# electrode_tester.net
KiCad netlist of a schematic drawn in EAGLE
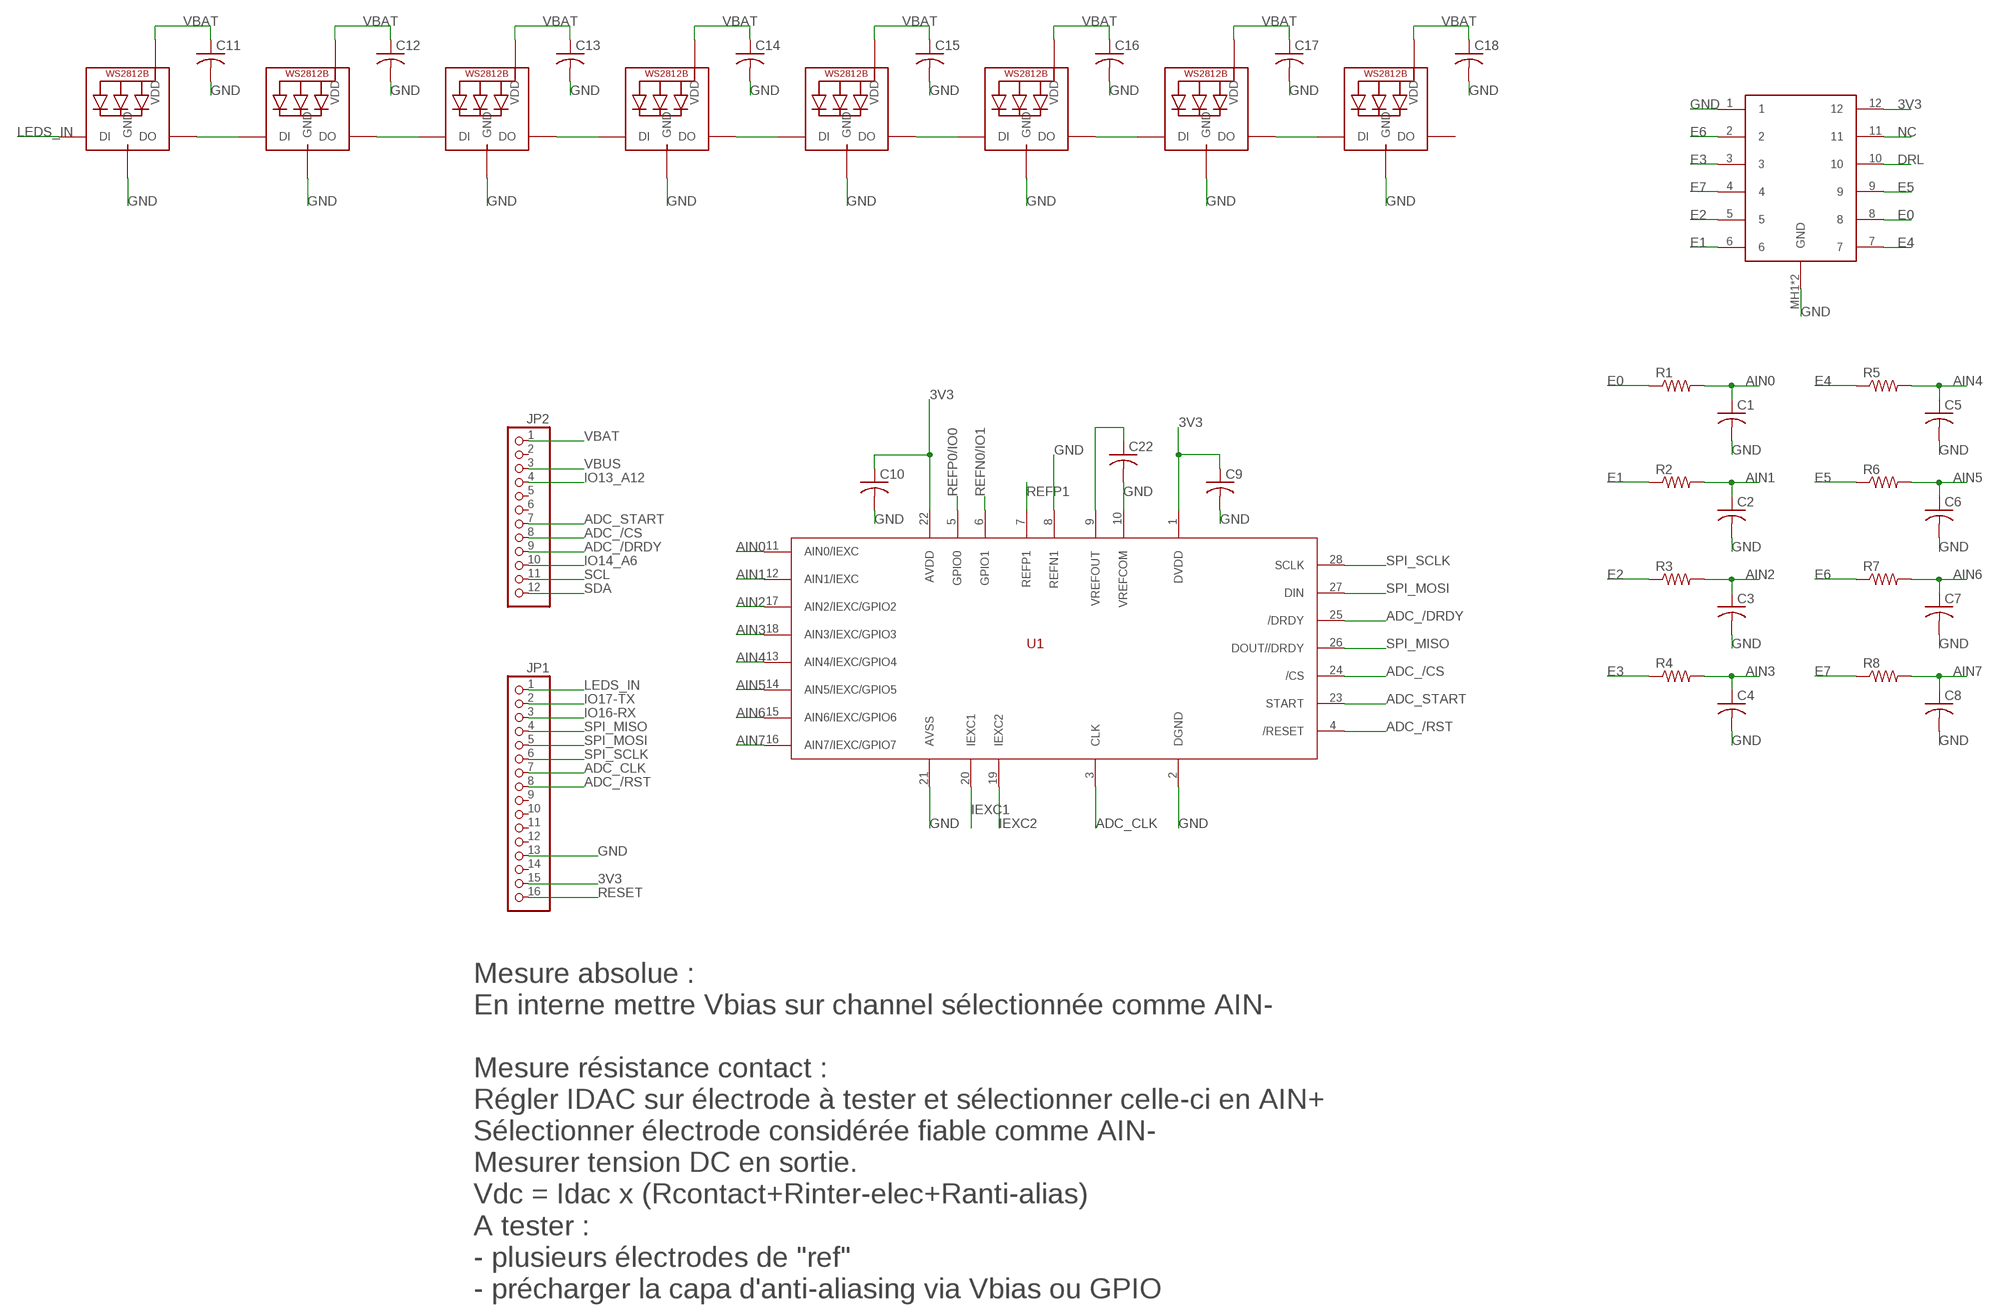
[diagram p0: schematic, sheet 1, part 1 of 2]
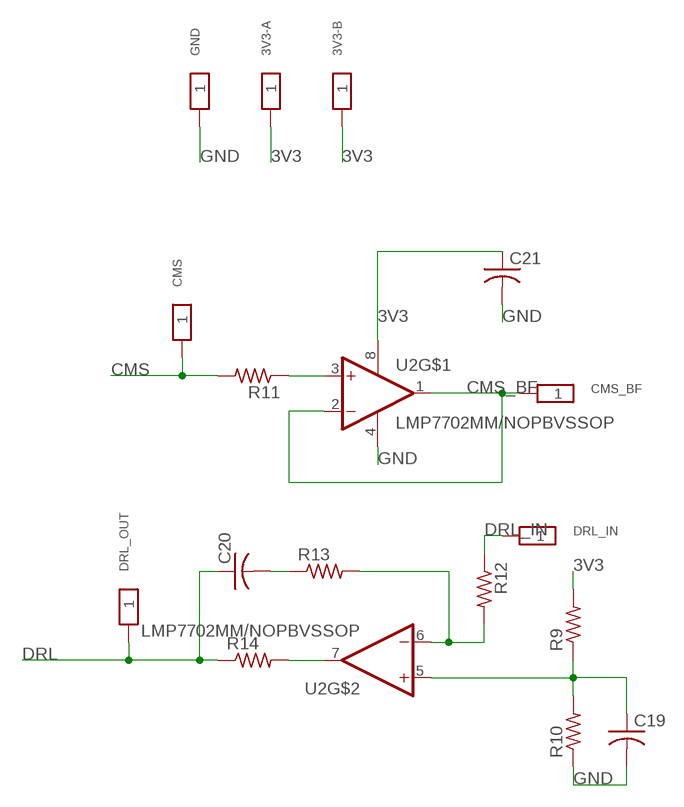
[diagram p1: schematic, sheet 1, part 2 of 2]

(export (version "E")
  (design (tool "Eeschema 10.0.6"))
  (components
    (comp (ref "3V3-A")
      (value "TESTPAD_PROG")
      (footprint "eagle-import:TP1.5MM")
      (libsource (lib "eagle-import") (part "TESTPAD_PROG"))
    )
    (comp (ref "3V3-B")
      (value "TESTPAD_PROG")
      (footprint "eagle-import:TP1.5MM")
      (libsource (lib "eagle-import") (part "TESTPAD_PROG"))
    )
    (comp (ref "C1")
      (value "C-USC0603")
      (footprint "eagle-import:C0603")
      (libsource (lib "eagle-import") (part "C-USC0603"))
    )
    (comp (ref "C2")
      (value "C-USC0603")
      (footprint "eagle-import:C0603")
      (libsource (lib "eagle-import") (part "C-USC0603"))
    )
    (comp (ref "C3")
      (value "C-USC0603")
      (footprint "eagle-import:C0603")
      (libsource (lib "eagle-import") (part "C-USC0603"))
    )
    (comp (ref "C4")
      (value "C-USC0603")
      (footprint "eagle-import:C0603")
      (libsource (lib "eagle-import") (part "C-USC0603"))
    )
    (comp (ref "C5")
      (value "C-USC0603")
      (footprint "eagle-import:C0603")
      (libsource (lib "eagle-import") (part "C-USC0603"))
    )
    (comp (ref "C6")
      (value "C-USC0603")
      (footprint "eagle-import:C0603")
      (libsource (lib "eagle-import") (part "C-USC0603"))
    )
    (comp (ref "C7")
      (value "C-USC0603")
      (footprint "eagle-import:C0603")
      (libsource (lib "eagle-import") (part "C-USC0603"))
    )
    (comp (ref "C8")
      (value "C-USC0603")
      (footprint "eagle-import:C0603")
      (libsource (lib "eagle-import") (part "C-USC0603"))
    )
    (comp (ref "C9")
      (value "C-USC0603")
      (footprint "eagle-import:C0603")
      (libsource (lib "eagle-import") (part "C-USC0603"))
    )
    (comp (ref "C10")
      (value "C-USC0603")
      (footprint "eagle-import:C0603")
      (libsource (lib "eagle-import") (part "C-USC0603"))
    )
    (comp (ref "C11")
      (value "C-USC0603")
      (footprint "eagle-import:C0603")
      (libsource (lib "eagle-import") (part "C-USC0603"))
    )
    (comp (ref "C12")
      (value "C-USC0603")
      (footprint "eagle-import:C0603")
      (libsource (lib "eagle-import") (part "C-USC0603"))
    )
    (comp (ref "C13")
      (value "C-USC0603")
      (footprint "eagle-import:C0603")
      (libsource (lib "eagle-import") (part "C-USC0603"))
    )
    (comp (ref "C14")
      (value "C-USC0603")
      (footprint "eagle-import:C0603")
      (libsource (lib "eagle-import") (part "C-USC0603"))
    )
    (comp (ref "C15")
      (value "C-USC0603")
      (footprint "eagle-import:C0603")
      (libsource (lib "eagle-import") (part "C-USC0603"))
    )
    (comp (ref "C16")
      (value "C-USC0603")
      (footprint "eagle-import:C0603")
      (libsource (lib "eagle-import") (part "C-USC0603"))
    )
    (comp (ref "C17")
      (value "C-USC0603")
      (footprint "eagle-import:C0603")
      (libsource (lib "eagle-import") (part "C-USC0603"))
    )
    (comp (ref "C18")
      (value "C-USC0603")
      (footprint "eagle-import:C0603")
      (libsource (lib "eagle-import") (part "C-USC0603"))
    )
    (comp (ref "C19")
      (value "C-USC0603")
      (footprint "eagle-import:C0603")
      (libsource (lib "eagle-import") (part "C-USC0603"))
    )
    (comp (ref "C20")
      (value "C-USC0603")
      (footprint "eagle-import:C0603")
      (libsource (lib "eagle-import") (part "C-USC0603"))
    )
    (comp (ref "C21")
      (value "C-USC0603")
      (footprint "eagle-import:C0603")
      (libsource (lib "eagle-import") (part "C-USC0603"))
    )
    (comp (ref "C22")
      (value "C-USC0603")
      (footprint "eagle-import:C0603")
      (libsource (lib "eagle-import") (part "C-USC0603"))
    )
    (comp (ref "CMS")
      (value "TESTPAD_PROG")
      (footprint "eagle-import:TP1.5MM")
      (libsource (lib "eagle-import") (part "TESTPAD_PROG"))
    )
    (comp (ref "CMS_BF")
      (value "TESTPAD_PROG")
      (footprint "eagle-import:TP1.5MM")
      (libsource (lib "eagle-import") (part "TESTPAD_PROG"))
    )
    (comp (ref "CONN1")
      (value "505110-1292")
      (footprint "eagle-import:505110-1292")
      (libsource (lib "eagle-import") (part "505110-1292"))
    )
    (comp (ref "DRL_IN")
      (value "TESTPAD_PROG")
      (footprint "eagle-import:TP1.5MM")
      (libsource (lib "eagle-import") (part "TESTPAD_PROG"))
    )
    (comp (ref "DRL_OUT")
      (value "TESTPAD_PROG")
      (footprint "eagle-import:TP1.5MM")
      (libsource (lib "eagle-import") (part "TESTPAD_PROG"))
    )
    (comp (ref "GND")
      (value "TESTPAD_PROG")
      (footprint "eagle-import:TP1.5MM")
      (libsource (lib "eagle-import") (part "TESTPAD_PROG"))
    )
    (comp (ref "JP1")
      (value "HEADER-1X16ROUND")
      (footprint "eagle-import:1X16_ROUND")
      (libsource (lib "eagle-import") (part "HEADER-1X16ROUND"))
    )
    (comp (ref "JP2")
      (value "HEADER-1X12")
      (footprint "eagle-import:1X12_ROUND")
      (libsource (lib "eagle-import") (part "HEADER-1X12"))
    )
    (comp (ref "LED1")
      (value "WS2812B5050")
      (footprint "eagle-import:WS2812B")
      (libsource (lib "eagle-import") (part "WS2812B5050"))
    )
    (comp (ref "LED2")
      (value "WS2812B5050")
      (footprint "eagle-import:WS2812B")
      (libsource (lib "eagle-import") (part "WS2812B5050"))
    )
    (comp (ref "LED3")
      (value "WS2812B5050")
      (footprint "eagle-import:WS2812B")
      (libsource (lib "eagle-import") (part "WS2812B5050"))
    )
    (comp (ref "LED4")
      (value "WS2812B5050")
      (footprint "eagle-import:WS2812B")
      (libsource (lib "eagle-import") (part "WS2812B5050"))
    )
    (comp (ref "LED5")
      (value "WS2812B5050")
      (footprint "eagle-import:WS2812B")
      (libsource (lib "eagle-import") (part "WS2812B5050"))
    )
    (comp (ref "LED6")
      (value "WS2812B5050")
      (footprint "eagle-import:WS2812B")
      (libsource (lib "eagle-import") (part "WS2812B5050"))
    )
    (comp (ref "LED7")
      (value "WS2812B5050")
      (footprint "eagle-import:WS2812B")
      (libsource (lib "eagle-import") (part "WS2812B5050"))
    )
    (comp (ref "LED8")
      (value "WS2812B5050")
      (footprint "eagle-import:WS2812B")
      (libsource (lib "eagle-import") (part "WS2812B5050"))
    )
    (comp (ref "R1")
      (value "R-US_R0603")
      (footprint "eagle-import:R0603")
      (libsource (lib "eagle-import") (part "R-US_R0603"))
    )
    (comp (ref "R2")
      (value "R-US_R0603")
      (footprint "eagle-import:R0603")
      (libsource (lib "eagle-import") (part "R-US_R0603"))
    )
    (comp (ref "R3")
      (value "R-US_R0603")
      (footprint "eagle-import:R0603")
      (libsource (lib "eagle-import") (part "R-US_R0603"))
    )
    (comp (ref "R4")
      (value "R-US_R0603")
      (footprint "eagle-import:R0603")
      (libsource (lib "eagle-import") (part "R-US_R0603"))
    )
    (comp (ref "R5")
      (value "R-US_R0603")
      (footprint "eagle-import:R0603")
      (libsource (lib "eagle-import") (part "R-US_R0603"))
    )
    (comp (ref "R6")
      (value "R-US_R0603")
      (footprint "eagle-import:R0603")
      (libsource (lib "eagle-import") (part "R-US_R0603"))
    )
    (comp (ref "R7")
      (value "R-US_R0603")
      (footprint "eagle-import:R0603")
      (libsource (lib "eagle-import") (part "R-US_R0603"))
    )
    (comp (ref "R8")
      (value "R-US_R0603")
      (footprint "eagle-import:R0603")
      (libsource (lib "eagle-import") (part "R-US_R0603"))
    )
    (comp (ref "R9")
      (value "R-US_R0603")
      (footprint "eagle-import:R0603")
      (libsource (lib "eagle-import") (part "R-US_R0603"))
    )
    (comp (ref "R10")
      (value "R-US_R0603")
      (footprint "eagle-import:R0603")
      (libsource (lib "eagle-import") (part "R-US_R0603"))
    )
    (comp (ref "R11")
      (value "R-US_R0603")
      (footprint "eagle-import:R0603")
      (libsource (lib "eagle-import") (part "R-US_R0603"))
    )
    (comp (ref "R12")
      (value "R-US_R0603")
      (footprint "eagle-import:R0603")
      (libsource (lib "eagle-import") (part "R-US_R0603"))
    )
    (comp (ref "R13")
      (value "R-US_R0603")
      (footprint "eagle-import:R0603")
      (libsource (lib "eagle-import") (part "R-US_R0603"))
    )
    (comp (ref "R14")
      (value "R-US_R0603")
      (footprint "eagle-import:R0603")
      (libsource (lib "eagle-import") (part "R-US_R0603"))
    )
    (comp (ref "U1")
      (value "ADS1248")
      (footprint "eagle-import:TSSOP28")
      (libsource (lib "eagle-import") (part "ADS1248"))
    )
    (comp (ref "U2")
      (value "LMP7702MM/NOPBVSSOP")
      (footprint "eagle-import:VSSOP8")
      (fields (field (name "MF") "Texas Instruments") (field (name "MP") "LMP7702MM/NOPB"))
      (libsource (lib "eagle-import") (part "LMP7702MM/NOPBVSSOP"))
    )
  )
  (nets
    (net (code "1") (name "/3V3") (class "Default")
      (node (ref "3V3-A") (pin "1") (pinfunction "1_1") (pintype "bidirectional"))
      (node (ref "3V3-B") (pin "1") (pinfunction "1_1") (pintype "bidirectional"))
      (node (ref "C10") (pin "1") (pinfunction "1_1") (pintype "passive"))
      (node (ref "C21") (pin "1") (pinfunction "1_1") (pintype "passive"))
      (node (ref "C9") (pin "1") (pinfunction "1_1") (pintype "passive"))
      (node (ref "CONN1") (pin "12") (pinfunction "12_12") (pintype "bidirectional"))
      (node (ref "JP1") (pin "15") (pinfunction "15_15") (pintype "passive"))
      (node (ref "R9") (pin "2") (pinfunction "2_2") (pintype "passive"))
      (node (ref "U1") (pin "1") (pinfunction "DVDD_1") (pintype "bidirectional"))
      (node (ref "U1") (pin "22") (pinfunction "AVDD_22") (pintype "bidirectional"))
      (node (ref "U2") (pin "8") (pinfunction "V+_8") (pintype "power_in"))
    )
    (net (code "2") (name "/ADC_CLK") (class "Default")
      (node (ref "JP1") (pin "7") (pinfunction "7_7") (pintype "passive"))
      (node (ref "U1") (pin "3") (pinfunction "CLK_3") (pintype "bidirectional"))
    )
    (net (code "3") (name "/ADC_START") (class "Default")
      (node (ref "JP2") (pin "7") (pinfunction "7_7") (pintype "passive"))
      (node (ref "U1") (pin "23") (pinfunction "START_23") (pintype "bidirectional"))
    )
    (net (code "4") (name "/ADC_{slash}CS") (class "Default")
      (node (ref "JP2") (pin "8") (pinfunction "8_8") (pintype "passive"))
      (node (ref "U1") (pin "24") (pinfunction "/CS_24") (pintype "bidirectional"))
    )
    (net (code "5") (name "/ADC_{slash}DRDY") (class "Default")
      (node (ref "JP2") (pin "9") (pinfunction "9_9") (pintype "passive"))
      (node (ref "U1") (pin "25") (pinfunction "/DRDY_25") (pintype "bidirectional"))
    )
    (net (code "6") (name "/ADC_{slash}RST") (class "Default")
      (node (ref "JP1") (pin "8") (pinfunction "8_8") (pintype "passive"))
      (node (ref "U1") (pin "4") (pinfunction "/RESET_4") (pintype "bidirectional"))
    )
    (net (code "7") (name "/AIN0") (class "Default")
      (node (ref "C1") (pin "1") (pinfunction "1_1") (pintype "passive"))
      (node (ref "R1") (pin "2") (pinfunction "2_2") (pintype "passive"))
      (node (ref "U1") (pin "11") (pinfunction "AIN0/IEXC_11") (pintype "bidirectional"))
    )
    (net (code "8") (name "/AIN1") (class "Default")
      (node (ref "C2") (pin "1") (pinfunction "1_1") (pintype "passive"))
      (node (ref "R2") (pin "2") (pinfunction "2_2") (pintype "passive"))
      (node (ref "U1") (pin "12") (pinfunction "AIN1/IEXC_12") (pintype "bidirectional"))
    )
    (net (code "9") (name "/AIN2") (class "Default")
      (node (ref "C3") (pin "1") (pinfunction "1_1") (pintype "passive"))
      (node (ref "R3") (pin "2") (pinfunction "2_2") (pintype "passive"))
      (node (ref "U1") (pin "17") (pinfunction "AIN2/IEXC/GPIO2_17") (pintype "bidirectional"))
    )
    (net (code "10") (name "/AIN3") (class "Default")
      (node (ref "C4") (pin "1") (pinfunction "1_1") (pintype "passive"))
      (node (ref "R4") (pin "2") (pinfunction "2_2") (pintype "passive"))
      (node (ref "U1") (pin "18") (pinfunction "AIN3/IEXC/GPIO3_18") (pintype "bidirectional"))
    )
    (net (code "11") (name "/AIN4") (class "Default")
      (node (ref "C5") (pin "1") (pinfunction "1_1") (pintype "passive"))
      (node (ref "R5") (pin "2") (pinfunction "2_2") (pintype "passive"))
      (node (ref "U1") (pin "13") (pinfunction "AIN4/IEXC/GPIO4_13") (pintype "bidirectional"))
    )
    (net (code "12") (name "/AIN5") (class "Default")
      (node (ref "C6") (pin "1") (pinfunction "1_1") (pintype "passive"))
      (node (ref "R6") (pin "2") (pinfunction "2_2") (pintype "passive"))
      (node (ref "U1") (pin "14") (pinfunction "AIN5/IEXC/GPIO5_14") (pintype "bidirectional"))
    )
    (net (code "13") (name "/AIN6") (class "Default")
      (node (ref "C7") (pin "1") (pinfunction "1_1") (pintype "passive"))
      (node (ref "R7") (pin "2") (pinfunction "2_2") (pintype "passive"))
      (node (ref "U1") (pin "15") (pinfunction "AIN6/IEXC/GPIO6_15") (pintype "bidirectional"))
    )
    (net (code "14") (name "/AIN7") (class "Default")
      (node (ref "C8") (pin "1") (pinfunction "1_1") (pintype "passive"))
      (node (ref "R8") (pin "2") (pinfunction "2_2") (pintype "passive"))
      (node (ref "U1") (pin "16") (pinfunction "AIN7/IEXC/GPIO7_16") (pintype "bidirectional"))
    )
    (net (code "15") (name "/CMS") (class "Default")
      (node (ref "CMS") (pin "1") (pinfunction "1_1") (pintype "bidirectional"))
      (node (ref "R11") (pin "2") (pinfunction "2_2") (pintype "passive"))
    )
    (net (code "16") (name "/CMS_BF") (class "Default")
      (node (ref "CMS_BF") (pin "1") (pinfunction "1_1") (pintype "bidirectional"))
      (node (ref "U2") (pin "1") (pinfunction "OUT_1") (pintype "output"))
      (node (ref "U2") (pin "2") (pinfunction "-IN_2") (pintype "input"))
    )
    (net (code "17") (name "/DRL") (class "Default")
      (node (ref "C20") (pin "1") (pinfunction "1_1") (pintype "passive"))
      (node (ref "CONN1") (pin "10") (pinfunction "10_10") (pintype "bidirectional"))
      (node (ref "DRL_OUT") (pin "1") (pinfunction "1_1") (pintype "bidirectional"))
      (node (ref "R14") (pin "1") (pinfunction "1_1") (pintype "passive"))
    )
    (net (code "18") (name "/DRL_IN") (class "Default")
      (node (ref "DRL_IN") (pin "1") (pinfunction "1_1") (pintype "bidirectional"))
      (node (ref "R12") (pin "1") (pinfunction "1_1") (pintype "passive"))
    )
    (net (code "19") (name "/E0") (class "Default")
      (node (ref "CONN1") (pin "8") (pinfunction "8_8") (pintype "bidirectional"))
      (node (ref "R1") (pin "1") (pinfunction "1_1") (pintype "passive"))
    )
    (net (code "20") (name "/E1") (class "Default")
      (node (ref "CONN1") (pin "6") (pinfunction "6_6") (pintype "bidirectional"))
      (node (ref "R2") (pin "1") (pinfunction "1_1") (pintype "passive"))
    )
    (net (code "21") (name "/E2") (class "Default")
      (node (ref "CONN1") (pin "5") (pinfunction "5_5") (pintype "bidirectional"))
      (node (ref "R3") (pin "1") (pinfunction "1_1") (pintype "passive"))
    )
    (net (code "22") (name "/E3") (class "Default")
      (node (ref "CONN1") (pin "3") (pinfunction "3_3") (pintype "bidirectional"))
      (node (ref "R4") (pin "1") (pinfunction "1_1") (pintype "passive"))
    )
    (net (code "23") (name "/E4") (class "Default")
      (node (ref "CONN1") (pin "7") (pinfunction "7_7") (pintype "bidirectional"))
      (node (ref "R5") (pin "1") (pinfunction "1_1") (pintype "passive"))
    )
    (net (code "24") (name "/E5") (class "Default")
      (node (ref "CONN1") (pin "9") (pinfunction "9_9") (pintype "bidirectional"))
      (node (ref "R6") (pin "1") (pinfunction "1_1") (pintype "passive"))
    )
    (net (code "25") (name "/E6") (class "Default")
      (node (ref "CONN1") (pin "2") (pinfunction "2_2") (pintype "bidirectional"))
      (node (ref "R7") (pin "1") (pinfunction "1_1") (pintype "passive"))
    )
    (net (code "26") (name "/E7") (class "Default")
      (node (ref "CONN1") (pin "4") (pinfunction "4_4") (pintype "bidirectional"))
      (node (ref "R8") (pin "1") (pinfunction "1_1") (pintype "passive"))
    )
    (net (code "27") (name "/GND") (class "Default")
      (node (ref "C1") (pin "2") (pinfunction "2_2") (pintype "passive"))
      (node (ref "C10") (pin "2") (pinfunction "2_2") (pintype "passive"))
      (node (ref "C11") (pin "2") (pinfunction "2_2") (pintype "passive"))
      (node (ref "C12") (pin "2") (pinfunction "2_2") (pintype "passive"))
      (node (ref "C13") (pin "2") (pinfunction "2_2") (pintype "passive"))
      (node (ref "C14") (pin "2") (pinfunction "2_2") (pintype "passive"))
      (node (ref "C15") (pin "2") (pinfunction "2_2") (pintype "passive"))
      (node (ref "C16") (pin "2") (pinfunction "2_2") (pintype "passive"))
      (node (ref "C17") (pin "2") (pinfunction "2_2") (pintype "passive"))
      (node (ref "C18") (pin "2") (pinfunction "2_2") (pintype "passive"))
      (node (ref "C19") (pin "2") (pinfunction "2_2") (pintype "passive"))
      (node (ref "C2") (pin "2") (pinfunction "2_2") (pintype "passive"))
      (node (ref "C21") (pin "2") (pinfunction "2_2") (pintype "passive"))
      (node (ref "C22") (pin "2") (pinfunction "2_2") (pintype "passive"))
      (node (ref "C3") (pin "2") (pinfunction "2_2") (pintype "passive"))
      (node (ref "C4") (pin "2") (pinfunction "2_2") (pintype "passive"))
      (node (ref "C5") (pin "2") (pinfunction "2_2") (pintype "passive"))
      (node (ref "C6") (pin "2") (pinfunction "2_2") (pintype "passive"))
      (node (ref "C7") (pin "2") (pinfunction "2_2") (pintype "passive"))
      (node (ref "C8") (pin "2") (pinfunction "2_2") (pintype "passive"))
      (node (ref "C9") (pin "2") (pinfunction "2_2") (pintype "passive"))
      (node (ref "CONN1") (pin "1") (pinfunction "1_1") (pintype "bidirectional"))
      (node (ref "CONN1") (pin "MH1") (pinfunction "GND_MH1") (pintype "bidirectional"))
      (node (ref "CONN1") (pin "MH2") (pinfunction "GND_MH2") (pintype "bidirectional"))
      (node (ref "GND") (pin "1") (pinfunction "1_1") (pintype "bidirectional"))
      (node (ref "JP1") (pin "13") (pinfunction "13_13") (pintype "passive"))
      (node (ref "LED1") (pin "3-GND") (pinfunction "GND_3-GND") (pintype "power_in"))
      (node (ref "LED2") (pin "3-GND") (pinfunction "GND_3-GND") (pintype "power_in"))
      (node (ref "LED3") (pin "3-GND") (pinfunction "GND_3-GND") (pintype "power_in"))
      (node (ref "LED4") (pin "3-GND") (pinfunction "GND_3-GND") (pintype "power_in"))
      (node (ref "LED5") (pin "3-GND") (pinfunction "GND_3-GND") (pintype "power_in"))
      (node (ref "LED6") (pin "3-GND") (pinfunction "GND_3-GND") (pintype "power_in"))
      (node (ref "LED7") (pin "3-GND") (pinfunction "GND_3-GND") (pintype "power_in"))
      (node (ref "LED8") (pin "3-GND") (pinfunction "GND_3-GND") (pintype "power_in"))
      (node (ref "R10") (pin "1") (pinfunction "1_1") (pintype "passive"))
      (node (ref "U1") (pin "10") (pinfunction "VREFCOM_10") (pintype "bidirectional"))
      (node (ref "U1") (pin "2") (pinfunction "DGND_2") (pintype "bidirectional"))
      (node (ref "U1") (pin "21") (pinfunction "AVSS_21") (pintype "bidirectional"))
      (node (ref "U1") (pin "8") (pinfunction "REFN1_8") (pintype "bidirectional"))
      (node (ref "U2") (pin "4") (pinfunction "V-_4") (pintype "power_in"))
    )
    (net (code "28") (name "/IEXC1") (class "Default")
      (node (ref "U1") (pin "20") (pinfunction "IEXC1_20") (pintype "bidirectional"))
    )
    (net (code "29") (name "/IEXC2") (class "Default")
      (node (ref "U1") (pin "19") (pinfunction "IEXC2_19") (pintype "bidirectional"))
    )
    (net (code "30") (name "/IO13_A12") (class "Default")
      (node (ref "JP2") (pin "4") (pinfunction "4_4") (pintype "passive"))
    )
    (net (code "31") (name "/IO14_A6") (class "Default")
      (node (ref "JP2") (pin "10") (pinfunction "10_10") (pintype "passive"))
    )
    (net (code "32") (name "/IO16-RX") (class "Default")
      (node (ref "JP1") (pin "3") (pinfunction "3_3") (pintype "passive"))
    )
    (net (code "33") (name "/IO17-TX") (class "Default")
      (node (ref "JP1") (pin "2") (pinfunction "2_2") (pintype "passive"))
    )
    (net (code "34") (name "/LEDS_IN") (class "Default")
      (node (ref "JP1") (pin "1") (pinfunction "1_1") (pintype "passive"))
      (node (ref "LED1") (pin "4-DIN") (pinfunction "DI_4-DIN") (pintype "input"))
    )
    (net (code "35") (name "/NC") (class "Default")
      (node (ref "CONN1") (pin "11") (pinfunction "11_11") (pintype "bidirectional"))
    )
    (net (code "36") (name "/REFN0{slash}IO1") (class "Default")
      (node (ref "U1") (pin "6") (pinfunction "GPIO1_6") (pintype "bidirectional"))
    )
    (net (code "37") (name "/REFP0{slash}IO0") (class "Default")
      (node (ref "U1") (pin "5") (pinfunction "GPIO0_5") (pintype "bidirectional"))
    )
    (net (code "38") (name "/REFP1") (class "Default")
      (node (ref "U1") (pin "7") (pinfunction "REFP1_7") (pintype "bidirectional"))
    )
    (net (code "39") (name "/RESET") (class "Default")
      (node (ref "JP1") (pin "16") (pinfunction "16_16") (pintype "passive"))
    )
    (net (code "40") (name "/SCL") (class "Default")
      (node (ref "JP2") (pin "11") (pinfunction "11_11") (pintype "passive"))
    )
    (net (code "41") (name "/SDA") (class "Default")
      (node (ref "JP2") (pin "12") (pinfunction "12_12") (pintype "passive"))
    )
    (net (code "42") (name "/SPI_MISO") (class "Default")
      (node (ref "JP1") (pin "4") (pinfunction "4_4") (pintype "passive"))
      (node (ref "U1") (pin "26") (pinfunction "DOUT//DRDY_26") (pintype "bidirectional"))
    )
    (net (code "43") (name "/SPI_MOSI") (class "Default")
      (node (ref "JP1") (pin "5") (pinfunction "5_5") (pintype "passive"))
      (node (ref "U1") (pin "27") (pinfunction "DIN_27") (pintype "bidirectional"))
    )
    (net (code "44") (name "/SPI_SCLK") (class "Default")
      (node (ref "JP1") (pin "6") (pinfunction "6_6") (pintype "passive"))
      (node (ref "U1") (pin "28") (pinfunction "SCLK_28") (pintype "bidirectional"))
    )
    (net (code "45") (name "/VBAT") (class "Default")
      (node (ref "C11") (pin "1") (pinfunction "1_1") (pintype "passive"))
      (node (ref "C12") (pin "1") (pinfunction "1_1") (pintype "passive"))
      (node (ref "C13") (pin "1") (pinfunction "1_1") (pintype "passive"))
      (node (ref "C14") (pin "1") (pinfunction "1_1") (pintype "passive"))
      (node (ref "C15") (pin "1") (pinfunction "1_1") (pintype "passive"))
      (node (ref "C16") (pin "1") (pinfunction "1_1") (pintype "passive"))
      (node (ref "C17") (pin "1") (pinfunction "1_1") (pintype "passive"))
      (node (ref "C18") (pin "1") (pinfunction "1_1") (pintype "passive"))
      (node (ref "JP2") (pin "1") (pinfunction "1_1") (pintype "passive"))
      (node (ref "LED1") (pin "1-VDD") (pinfunction "VDD_1-VDD") (pintype "power_in"))
      (node (ref "LED2") (pin "1-VDD") (pinfunction "VDD_1-VDD") (pintype "power_in"))
      (node (ref "LED3") (pin "1-VDD") (pinfunction "VDD_1-VDD") (pintype "power_in"))
      (node (ref "LED4") (pin "1-VDD") (pinfunction "VDD_1-VDD") (pintype "power_in"))
      (node (ref "LED5") (pin "1-VDD") (pinfunction "VDD_1-VDD") (pintype "power_in"))
      (node (ref "LED6") (pin "1-VDD") (pinfunction "VDD_1-VDD") (pintype "power_in"))
      (node (ref "LED7") (pin "1-VDD") (pinfunction "VDD_1-VDD") (pintype "power_in"))
      (node (ref "LED8") (pin "1-VDD") (pinfunction "VDD_1-VDD") (pintype "power_in"))
    )
    (net (code "46") (name "/VBUS") (class "Default")
      (node (ref "JP2") (pin "3") (pinfunction "3_3") (pintype "passive"))
    )
    (net (code "47") (name "Net-(C20-Pad2)") (class "Default")
      (node (ref "C20") (pin "2") (pinfunction "2_2") (pintype "passive"))
      (node (ref "R13") (pin "1") (pinfunction "1_1") (pintype "passive"))
    )
    (net (code "48") (name "Net-(LED1-DO)") (class "Default")
      (node (ref "LED1") (pin "2-DOUT") (pinfunction "DO_2-DOUT") (pintype "output"))
      (node (ref "LED2") (pin "4-DIN") (pinfunction "DI_4-DIN") (pintype "input"))
    )
    (net (code "49") (name "Net-(LED2-DO)") (class "Default")
      (node (ref "LED2") (pin "2-DOUT") (pinfunction "DO_2-DOUT") (pintype "output"))
      (node (ref "LED3") (pin "4-DIN") (pinfunction "DI_4-DIN") (pintype "input"))
    )
    (net (code "50") (name "Net-(LED3-DO)") (class "Default")
      (node (ref "LED3") (pin "2-DOUT") (pinfunction "DO_2-DOUT") (pintype "output"))
      (node (ref "LED4") (pin "4-DIN") (pinfunction "DI_4-DIN") (pintype "input"))
    )
    (net (code "51") (name "Net-(LED4-DO)") (class "Default")
      (node (ref "LED4") (pin "2-DOUT") (pinfunction "DO_2-DOUT") (pintype "output"))
      (node (ref "LED5") (pin "4-DIN") (pinfunction "DI_4-DIN") (pintype "input"))
    )
    (net (code "52") (name "Net-(LED5-DO)") (class "Default")
      (node (ref "LED5") (pin "2-DOUT") (pinfunction "DO_2-DOUT") (pintype "output"))
      (node (ref "LED6") (pin "4-DIN") (pinfunction "DI_4-DIN") (pintype "input"))
    )
    (net (code "53") (name "Net-(LED6-DO)") (class "Default")
      (node (ref "LED6") (pin "2-DOUT") (pinfunction "DO_2-DOUT") (pintype "output"))
      (node (ref "LED7") (pin "4-DIN") (pinfunction "DI_4-DIN") (pintype "input"))
    )
    (net (code "54") (name "Net-(LED7-DO)") (class "Default")
      (node (ref "LED7") (pin "2-DOUT") (pinfunction "DO_2-DOUT") (pintype "output"))
      (node (ref "LED8") (pin "4-DIN") (pinfunction "DI_4-DIN") (pintype "input"))
    )
    (net (code "55") (name "Net-(U1-VREFOUT)") (class "Default")
      (node (ref "C22") (pin "1") (pinfunction "1_1") (pintype "passive"))
      (node (ref "U1") (pin "9") (pinfunction "VREFOUT_9") (pintype "bidirectional"))
    )
    (net (code "56") (name "Net-(U2A-+IN)") (class "Default")
      (node (ref "R11") (pin "1") (pinfunction "1_1") (pintype "passive"))
      (node (ref "U2") (pin "3") (pinfunction "+IN_3") (pintype "input"))
    )
    (net (code "57") (name "Net-(U2B-+IN)") (class "Default")
      (node (ref "C19") (pin "1") (pinfunction "1_1") (pintype "passive"))
      (node (ref "R10") (pin "2") (pinfunction "2_2") (pintype "passive"))
      (node (ref "R9") (pin "1") (pinfunction "1_1") (pintype "passive"))
      (node (ref "U2") (pin "5") (pinfunction "+IN_5") (pintype "input"))
    )
    (net (code "58") (name "Net-(U2B--IN)") (class "Default")
      (node (ref "R12") (pin "2") (pinfunction "2_2") (pintype "passive"))
      (node (ref "R13") (pin "2") (pinfunction "2_2") (pintype "passive"))
      (node (ref "U2") (pin "6") (pinfunction "-IN_6") (pintype "input"))
    )
    (net (code "59") (name "Net-(U2B-OUT)") (class "Default")
      (node (ref "R14") (pin "2") (pinfunction "2_2") (pintype "passive"))
      (node (ref "U2") (pin "7") (pinfunction "OUT_7") (pintype "output"))
    )
    (net (code "60") (name "unconnected-(JP1-Pad9)") (class "Default")
      (node (ref "JP1") (pin "9") (pinfunction "9_9") (pintype "passive"))
    )
    (net (code "61") (name "unconnected-(JP1-Pad10)") (class "Default")
      (node (ref "JP1") (pin "10") (pinfunction "10_10") (pintype "passive"))
    )
    (net (code "62") (name "unconnected-(JP1-Pad11)") (class "Default")
      (node (ref "JP1") (pin "11") (pinfunction "11_11") (pintype "passive"))
    )
    (net (code "63") (name "unconnected-(JP1-Pad12)") (class "Default")
      (node (ref "JP1") (pin "12") (pinfunction "12_12") (pintype "passive"))
    )
    (net (code "64") (name "unconnected-(JP1-Pad14)") (class "Default")
      (node (ref "JP1") (pin "14") (pinfunction "14_14") (pintype "passive"))
    )
    (net (code "65") (name "unconnected-(JP2-Pad2)") (class "Default")
      (node (ref "JP2") (pin "2") (pinfunction "2_2") (pintype "passive"))
    )
    (net (code "66") (name "unconnected-(JP2-Pad5)") (class "Default")
      (node (ref "JP2") (pin "5") (pinfunction "5_5") (pintype "passive"))
    )
    (net (code "67") (name "unconnected-(JP2-Pad6)") (class "Default")
      (node (ref "JP2") (pin "6") (pinfunction "6_6") (pintype "passive"))
    )
    (net (code "68") (name "unconnected-(LED8-DO-Pad2-DOUT)") (class "Default")
      (node (ref "LED8") (pin "2-DOUT") (pinfunction "DO_2-DOUT") (pintype "output"))
    )
  )
)
